# Hex_BlinkyTile.net
KiCad netlist of a schematic drawn in EAGLE
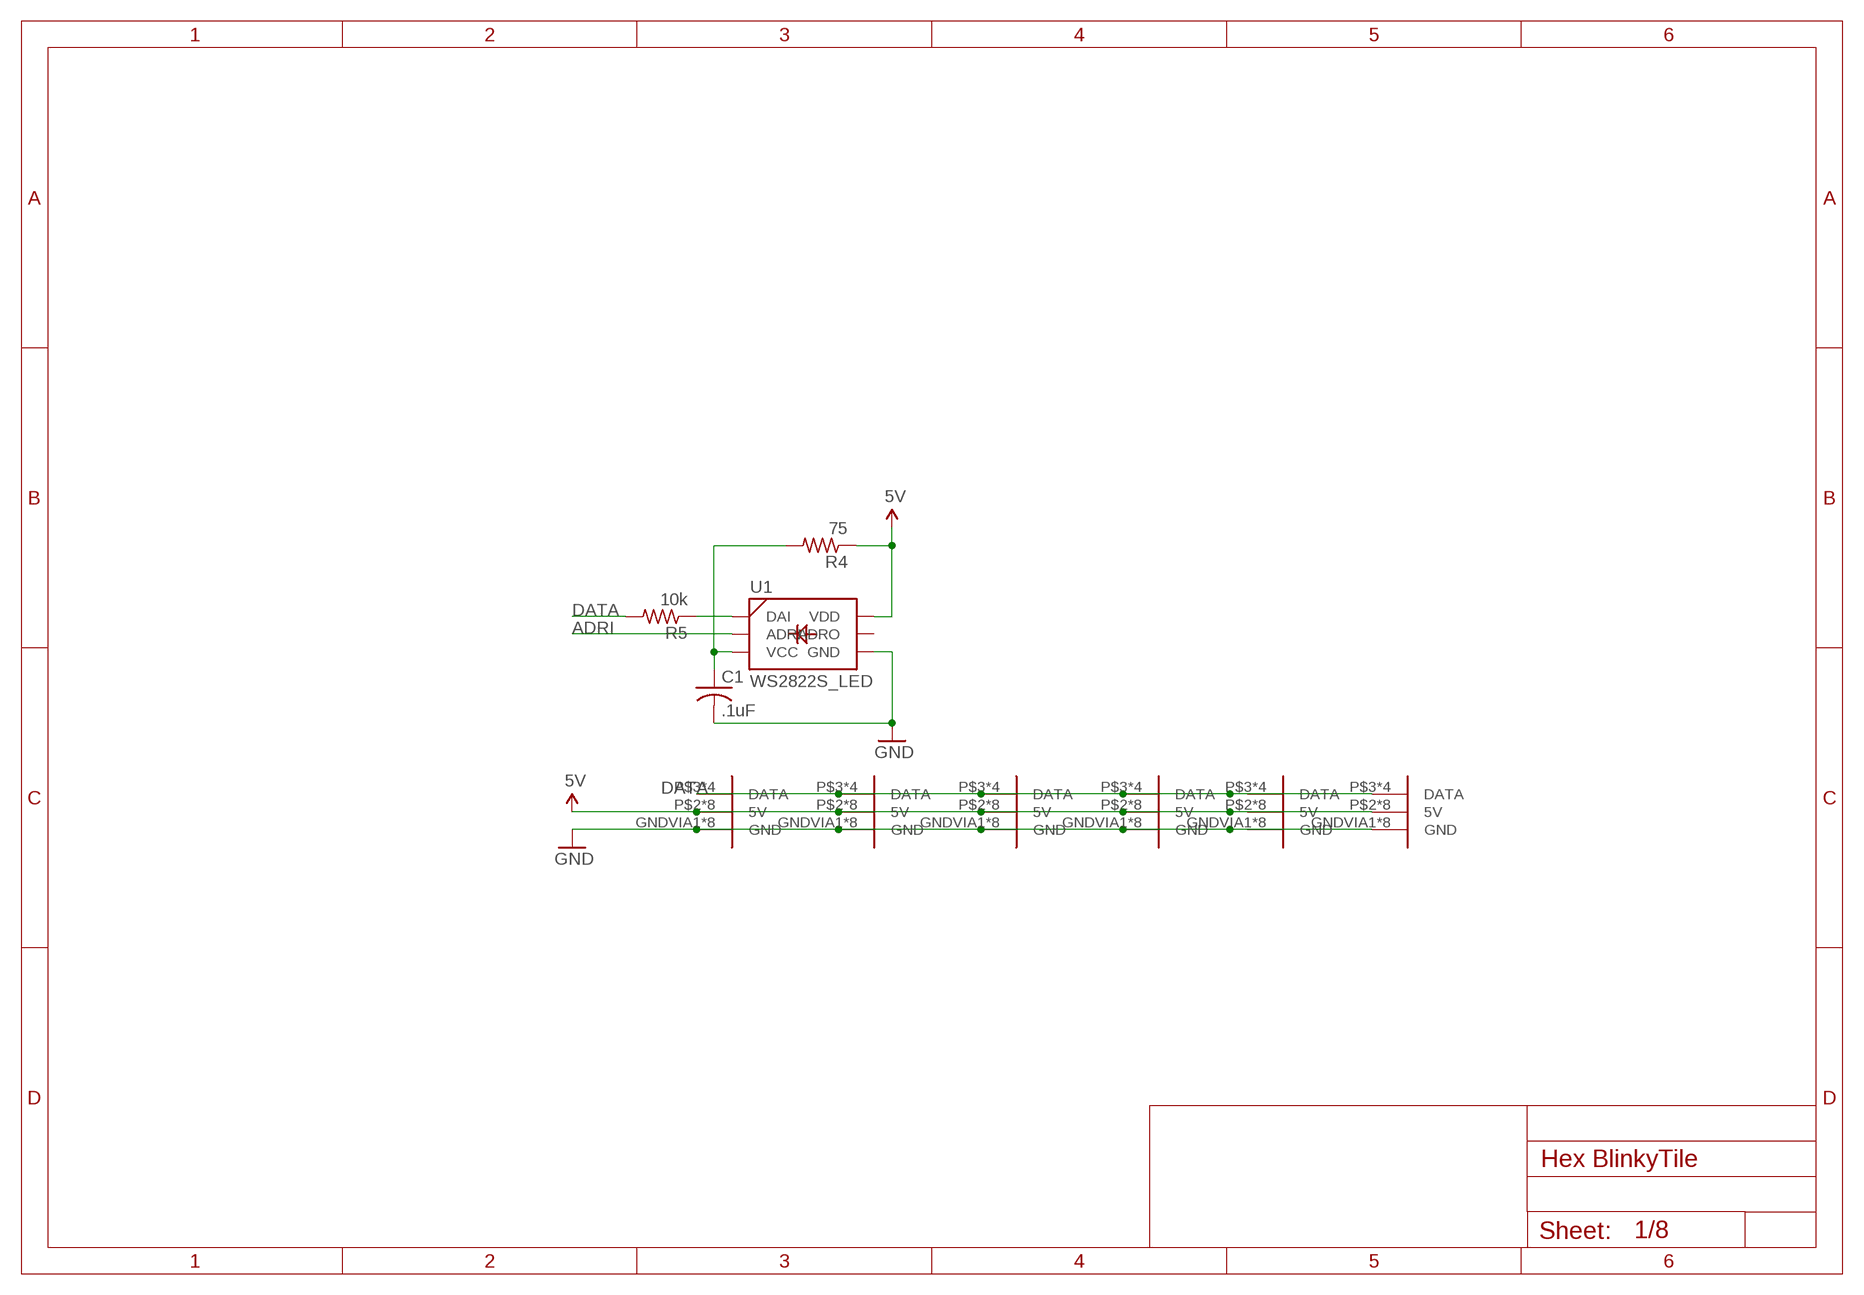
[diagram p0: schematic, sheet 1]

(export (version "E")
  (design (tool "Eeschema 10.0.6"))
  (components
    (comp (ref "C1")
      (value ".1uF")
      (footprint "eagle-import:C0603")
      (libsource (lib "eagle-import") (part "C-USC0603"))
    )
    (comp (ref "R4")
      (value "75")
      (footprint "eagle-import:R0603")
      (libsource (lib "eagle-import") (part "R-US_R0603"))
    )
    (comp (ref "R5")
      (value "10k")
      (footprint "eagle-import:R0603")
      (libsource (lib "eagle-import") (part "R-US_R0603"))
    )
    (comp (ref "U$1")
      (value "D_EDGEMOD")
      (footprint "eagle-import:D_EDGE_SLOT_MOD")
      (libsource (lib "eagle-import") (part "D_EDGEMOD"))
    )
    (comp (ref "U$2")
      (value "D_EDGEMOD")
      (footprint "eagle-import:D_EDGE_SLOT_MOD")
      (libsource (lib "eagle-import") (part "D_EDGEMOD"))
    )
    (comp (ref "U$3")
      (value "D_EDGEMOD")
      (footprint "eagle-import:D_EDGE_SLOT_MOD")
      (libsource (lib "eagle-import") (part "D_EDGEMOD"))
    )
    (comp (ref "U$4")
      (value "D_EDGEMOD")
      (footprint "eagle-import:D_EDGE_SLOT_MOD")
      (libsource (lib "eagle-import") (part "D_EDGEMOD"))
    )
    (comp (ref "U$5")
      (value "D_EDGEMOD")
      (footprint "eagle-import:D_EDGE_SLOT_MOD")
      (libsource (lib "eagle-import") (part "D_EDGEMOD"))
    )
    (comp (ref "U$6")
      (value "D_EDGEMOD")
      (footprint "eagle-import:D_EDGE_SLOT_MOD")
      (libsource (lib "eagle-import") (part "D_EDGEMOD"))
    )
    (comp (ref "U1")
      (value "WS2822S_LED")
      (footprint "eagle-import:WS2822S_LED")
      (libsource (lib "eagle-import") (part "WS2822S_LED"))
    )
  )
  (nets
    (net (code "1") (name "5V") (class "Default")
      (node (ref "R4") (pin "1") (pinfunction "1_1") (pintype "passive"))
      (node (ref "U$1") (pin "P$2") (pinfunction "5V_P$2") (pintype "bidirectional"))
      (node (ref "U$1") (pin "P$4") (pinfunction "5V_P$4") (pintype "bidirectional"))
      (node (ref "U$1") (pin "P$7") (pinfunction "5V_P$7") (pintype "bidirectional"))
      (node (ref "U$1") (pin "P$9") (pinfunction "5V_P$9") (pintype "bidirectional"))
      (node (ref "U$1") (pin "PWRVIA1") (pinfunction "5V_PWRVIA1") (pintype "bidirectional"))
      (node (ref "U$1") (pin "PWRVIA3") (pinfunction "5V_PWRVIA3") (pintype "bidirectional"))
      (node (ref "U$1") (pin "PWRVIA4") (pinfunction "5V_PWRVIA4") (pintype "bidirectional"))
      (node (ref "U$1") (pin "PWRVIA6") (pinfunction "5V_PWRVIA6") (pintype "bidirectional"))
      (node (ref "U$2") (pin "P$2") (pinfunction "5V_P$2") (pintype "bidirectional"))
      (node (ref "U$2") (pin "P$4") (pinfunction "5V_P$4") (pintype "bidirectional"))
      (node (ref "U$2") (pin "P$7") (pinfunction "5V_P$7") (pintype "bidirectional"))
      (node (ref "U$2") (pin "P$9") (pinfunction "5V_P$9") (pintype "bidirectional"))
      (node (ref "U$2") (pin "PWRVIA1") (pinfunction "5V_PWRVIA1") (pintype "bidirectional"))
      (node (ref "U$2") (pin "PWRVIA3") (pinfunction "5V_PWRVIA3") (pintype "bidirectional"))
      (node (ref "U$2") (pin "PWRVIA4") (pinfunction "5V_PWRVIA4") (pintype "bidirectional"))
      (node (ref "U$2") (pin "PWRVIA6") (pinfunction "5V_PWRVIA6") (pintype "bidirectional"))
      (node (ref "U$3") (pin "P$2") (pinfunction "5V_P$2") (pintype "bidirectional"))
      (node (ref "U$3") (pin "P$4") (pinfunction "5V_P$4") (pintype "bidirectional"))
      (node (ref "U$3") (pin "P$7") (pinfunction "5V_P$7") (pintype "bidirectional"))
      (node (ref "U$3") (pin "P$9") (pinfunction "5V_P$9") (pintype "bidirectional"))
      (node (ref "U$3") (pin "PWRVIA1") (pinfunction "5V_PWRVIA1") (pintype "bidirectional"))
      (node (ref "U$3") (pin "PWRVIA3") (pinfunction "5V_PWRVIA3") (pintype "bidirectional"))
      (node (ref "U$3") (pin "PWRVIA4") (pinfunction "5V_PWRVIA4") (pintype "bidirectional"))
      (node (ref "U$3") (pin "PWRVIA6") (pinfunction "5V_PWRVIA6") (pintype "bidirectional"))
      (node (ref "U$4") (pin "P$2") (pinfunction "5V_P$2") (pintype "bidirectional"))
      (node (ref "U$4") (pin "P$4") (pinfunction "5V_P$4") (pintype "bidirectional"))
      (node (ref "U$4") (pin "P$7") (pinfunction "5V_P$7") (pintype "bidirectional"))
      (node (ref "U$4") (pin "P$9") (pinfunction "5V_P$9") (pintype "bidirectional"))
      (node (ref "U$4") (pin "PWRVIA1") (pinfunction "5V_PWRVIA1") (pintype "bidirectional"))
      (node (ref "U$4") (pin "PWRVIA3") (pinfunction "5V_PWRVIA3") (pintype "bidirectional"))
      (node (ref "U$4") (pin "PWRVIA4") (pinfunction "5V_PWRVIA4") (pintype "bidirectional"))
      (node (ref "U$4") (pin "PWRVIA6") (pinfunction "5V_PWRVIA6") (pintype "bidirectional"))
      (node (ref "U$5") (pin "P$2") (pinfunction "5V_P$2") (pintype "bidirectional"))
      (node (ref "U$5") (pin "P$4") (pinfunction "5V_P$4") (pintype "bidirectional"))
      (node (ref "U$5") (pin "P$7") (pinfunction "5V_P$7") (pintype "bidirectional"))
      (node (ref "U$5") (pin "P$9") (pinfunction "5V_P$9") (pintype "bidirectional"))
      (node (ref "U$5") (pin "PWRVIA1") (pinfunction "5V_PWRVIA1") (pintype "bidirectional"))
      (node (ref "U$5") (pin "PWRVIA3") (pinfunction "5V_PWRVIA3") (pintype "bidirectional"))
      (node (ref "U$5") (pin "PWRVIA4") (pinfunction "5V_PWRVIA4") (pintype "bidirectional"))
      (node (ref "U$5") (pin "PWRVIA6") (pinfunction "5V_PWRVIA6") (pintype "bidirectional"))
      (node (ref "U$6") (pin "P$2") (pinfunction "5V_P$2") (pintype "bidirectional"))
      (node (ref "U$6") (pin "P$4") (pinfunction "5V_P$4") (pintype "bidirectional"))
      (node (ref "U$6") (pin "P$7") (pinfunction "5V_P$7") (pintype "bidirectional"))
      (node (ref "U$6") (pin "P$9") (pinfunction "5V_P$9") (pintype "bidirectional"))
      (node (ref "U$6") (pin "PWRVIA1") (pinfunction "5V_PWRVIA1") (pintype "bidirectional"))
      (node (ref "U$6") (pin "PWRVIA3") (pinfunction "5V_PWRVIA3") (pintype "bidirectional"))
      (node (ref "U$6") (pin "PWRVIA4") (pinfunction "5V_PWRVIA4") (pintype "bidirectional"))
      (node (ref "U$6") (pin "PWRVIA6") (pinfunction "5V_PWRVIA6") (pintype "bidirectional"))
      (node (ref "U1") (pin "6") (pinfunction "VDD_6") (pintype "power_in"))
    )
    (net (code "2") (name "ADRI") (class "Default")
      (node (ref "U1") (pin "2") (pinfunction "ADRI_2") (pintype "input"))
    )
    (net (code "3") (name "DATA") (class "Default")
      (node (ref "R5") (pin "2") (pinfunction "2_2") (pintype "passive"))
      (node (ref "U$1") (pin "P$3") (pinfunction "DATA_P$3") (pintype "bidirectional"))
      (node (ref "U$1") (pin "P$8") (pinfunction "DATA_P$8") (pintype "bidirectional"))
      (node (ref "U$1") (pin "SIGVIA1") (pinfunction "DATA_SIGVIA1") (pintype "bidirectional"))
      (node (ref "U$1") (pin "SIGVIA3") (pinfunction "DATA_SIGVIA3") (pintype "bidirectional"))
      (node (ref "U$2") (pin "P$3") (pinfunction "DATA_P$3") (pintype "bidirectional"))
      (node (ref "U$2") (pin "P$8") (pinfunction "DATA_P$8") (pintype "bidirectional"))
      (node (ref "U$2") (pin "SIGVIA1") (pinfunction "DATA_SIGVIA1") (pintype "bidirectional"))
      (node (ref "U$2") (pin "SIGVIA3") (pinfunction "DATA_SIGVIA3") (pintype "bidirectional"))
      (node (ref "U$3") (pin "P$3") (pinfunction "DATA_P$3") (pintype "bidirectional"))
      (node (ref "U$3") (pin "P$8") (pinfunction "DATA_P$8") (pintype "bidirectional"))
      (node (ref "U$3") (pin "SIGVIA1") (pinfunction "DATA_SIGVIA1") (pintype "bidirectional"))
      (node (ref "U$3") (pin "SIGVIA3") (pinfunction "DATA_SIGVIA3") (pintype "bidirectional"))
      (node (ref "U$4") (pin "P$3") (pinfunction "DATA_P$3") (pintype "bidirectional"))
      (node (ref "U$4") (pin "P$8") (pinfunction "DATA_P$8") (pintype "bidirectional"))
      (node (ref "U$4") (pin "SIGVIA1") (pinfunction "DATA_SIGVIA1") (pintype "bidirectional"))
      (node (ref "U$4") (pin "SIGVIA3") (pinfunction "DATA_SIGVIA3") (pintype "bidirectional"))
      (node (ref "U$5") (pin "P$3") (pinfunction "DATA_P$3") (pintype "bidirectional"))
      (node (ref "U$5") (pin "P$8") (pinfunction "DATA_P$8") (pintype "bidirectional"))
      (node (ref "U$5") (pin "SIGVIA1") (pinfunction "DATA_SIGVIA1") (pintype "bidirectional"))
      (node (ref "U$5") (pin "SIGVIA3") (pinfunction "DATA_SIGVIA3") (pintype "bidirectional"))
      (node (ref "U$6") (pin "P$3") (pinfunction "DATA_P$3") (pintype "bidirectional"))
      (node (ref "U$6") (pin "P$8") (pinfunction "DATA_P$8") (pintype "bidirectional"))
      (node (ref "U$6") (pin "SIGVIA1") (pinfunction "DATA_SIGVIA1") (pintype "bidirectional"))
      (node (ref "U$6") (pin "SIGVIA3") (pinfunction "DATA_SIGVIA3") (pintype "bidirectional"))
    )
    (net (code "4") (name "GND") (class "Default")
      (node (ref "C1") (pin "2") (pinfunction "2_2") (pintype "passive"))
      (node (ref "U$1") (pin "GNDVIA1") (pinfunction "GND_GNDVIA1") (pintype "bidirectional"))
      (node (ref "U$1") (pin "GNDVIA3") (pinfunction "GND_GNDVIA3") (pintype "bidirectional"))
      (node (ref "U$1") (pin "GNDVIA4") (pinfunction "GND_GNDVIA4") (pintype "bidirectional"))
      (node (ref "U$1") (pin "GNDVIA6") (pinfunction "GND_GNDVIA6") (pintype "bidirectional"))
      (node (ref "U$1") (pin "P$1") (pinfunction "GND_P$1") (pintype "bidirectional"))
      (node (ref "U$1") (pin "P$10") (pinfunction "GND_P$10") (pintype "bidirectional"))
      (node (ref "U$1") (pin "P$5") (pinfunction "GND_P$5") (pintype "bidirectional"))
      (node (ref "U$1") (pin "P$6") (pinfunction "GND_P$6") (pintype "bidirectional"))
      (node (ref "U$2") (pin "GNDVIA1") (pinfunction "GND_GNDVIA1") (pintype "bidirectional"))
      (node (ref "U$2") (pin "GNDVIA3") (pinfunction "GND_GNDVIA3") (pintype "bidirectional"))
      (node (ref "U$2") (pin "GNDVIA4") (pinfunction "GND_GNDVIA4") (pintype "bidirectional"))
      (node (ref "U$2") (pin "GNDVIA6") (pinfunction "GND_GNDVIA6") (pintype "bidirectional"))
      (node (ref "U$2") (pin "P$1") (pinfunction "GND_P$1") (pintype "bidirectional"))
      (node (ref "U$2") (pin "P$10") (pinfunction "GND_P$10") (pintype "bidirectional"))
      (node (ref "U$2") (pin "P$5") (pinfunction "GND_P$5") (pintype "bidirectional"))
      (node (ref "U$2") (pin "P$6") (pinfunction "GND_P$6") (pintype "bidirectional"))
      (node (ref "U$3") (pin "GNDVIA1") (pinfunction "GND_GNDVIA1") (pintype "bidirectional"))
      (node (ref "U$3") (pin "GNDVIA3") (pinfunction "GND_GNDVIA3") (pintype "bidirectional"))
      (node (ref "U$3") (pin "GNDVIA4") (pinfunction "GND_GNDVIA4") (pintype "bidirectional"))
      (node (ref "U$3") (pin "GNDVIA6") (pinfunction "GND_GNDVIA6") (pintype "bidirectional"))
      (node (ref "U$3") (pin "P$1") (pinfunction "GND_P$1") (pintype "bidirectional"))
      (node (ref "U$3") (pin "P$10") (pinfunction "GND_P$10") (pintype "bidirectional"))
      (node (ref "U$3") (pin "P$5") (pinfunction "GND_P$5") (pintype "bidirectional"))
      (node (ref "U$3") (pin "P$6") (pinfunction "GND_P$6") (pintype "bidirectional"))
      (node (ref "U$4") (pin "GNDVIA1") (pinfunction "GND_GNDVIA1") (pintype "bidirectional"))
      (node (ref "U$4") (pin "GNDVIA3") (pinfunction "GND_GNDVIA3") (pintype "bidirectional"))
      (node (ref "U$4") (pin "GNDVIA4") (pinfunction "GND_GNDVIA4") (pintype "bidirectional"))
      (node (ref "U$4") (pin "GNDVIA6") (pinfunction "GND_GNDVIA6") (pintype "bidirectional"))
      (node (ref "U$4") (pin "P$1") (pinfunction "GND_P$1") (pintype "bidirectional"))
      (node (ref "U$4") (pin "P$10") (pinfunction "GND_P$10") (pintype "bidirectional"))
      (node (ref "U$4") (pin "P$5") (pinfunction "GND_P$5") (pintype "bidirectional"))
      (node (ref "U$4") (pin "P$6") (pinfunction "GND_P$6") (pintype "bidirectional"))
      (node (ref "U$5") (pin "GNDVIA1") (pinfunction "GND_GNDVIA1") (pintype "bidirectional"))
      (node (ref "U$5") (pin "GNDVIA3") (pinfunction "GND_GNDVIA3") (pintype "bidirectional"))
      (node (ref "U$5") (pin "GNDVIA4") (pinfunction "GND_GNDVIA4") (pintype "bidirectional"))
      (node (ref "U$5") (pin "GNDVIA6") (pinfunction "GND_GNDVIA6") (pintype "bidirectional"))
      (node (ref "U$5") (pin "P$1") (pinfunction "GND_P$1") (pintype "bidirectional"))
      (node (ref "U$5") (pin "P$10") (pinfunction "GND_P$10") (pintype "bidirectional"))
      (node (ref "U$5") (pin "P$5") (pinfunction "GND_P$5") (pintype "bidirectional"))
      (node (ref "U$5") (pin "P$6") (pinfunction "GND_P$6") (pintype "bidirectional"))
      (node (ref "U$6") (pin "GNDVIA1") (pinfunction "GND_GNDVIA1") (pintype "bidirectional"))
      (node (ref "U$6") (pin "GNDVIA3") (pinfunction "GND_GNDVIA3") (pintype "bidirectional"))
      (node (ref "U$6") (pin "GNDVIA4") (pinfunction "GND_GNDVIA4") (pintype "bidirectional"))
      (node (ref "U$6") (pin "GNDVIA6") (pinfunction "GND_GNDVIA6") (pintype "bidirectional"))
      (node (ref "U$6") (pin "P$1") (pinfunction "GND_P$1") (pintype "bidirectional"))
      (node (ref "U$6") (pin "P$10") (pinfunction "GND_P$10") (pintype "bidirectional"))
      (node (ref "U$6") (pin "P$5") (pinfunction "GND_P$5") (pintype "bidirectional"))
      (node (ref "U$6") (pin "P$6") (pinfunction "GND_P$6") (pintype "bidirectional"))
      (node (ref "U1") (pin "4") (pinfunction "GND_4") (pintype "power_in"))
    )
    (net (code "5") (name "Net-(U1-DAI)") (class "Default")
      (node (ref "R5") (pin "1") (pinfunction "1_1") (pintype "passive"))
      (node (ref "U1") (pin "1") (pinfunction "DAI_1") (pintype "input"))
    )
    (net (code "6") (name "Net-(U1-VCC)") (class "Default")
      (node (ref "C1") (pin "1") (pinfunction "1_1") (pintype "passive"))
      (node (ref "R4") (pin "2") (pinfunction "2_2") (pintype "passive"))
      (node (ref "U1") (pin "3") (pinfunction "VCC_3") (pintype "power_in"))
    )
    (net (code "7") (name "unconnected-(U1-ADRO-Pad5)") (class "Default")
      (node (ref "U1") (pin "5") (pinfunction "ADRO_5") (pintype "output"))
    )
  )
)
